# SNES_RGBAmp_1Chip03.net
KiCad netlist of a schematic drawn in EAGLE
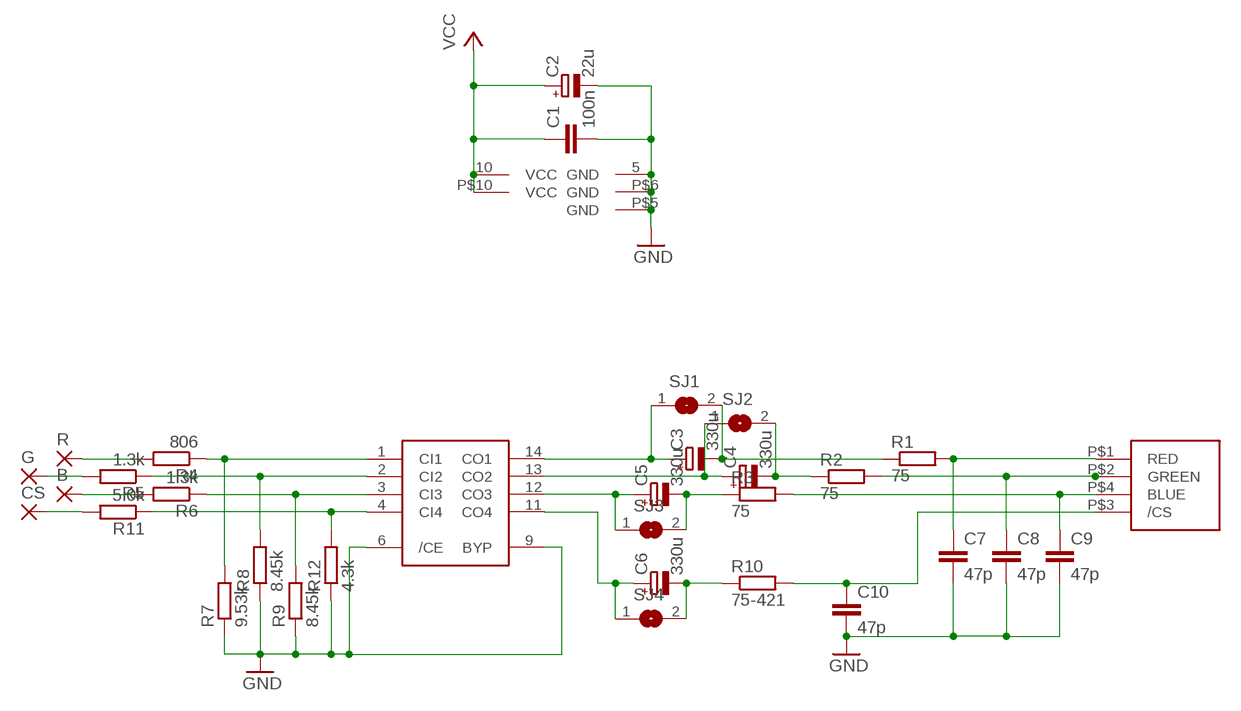
[diagram p0: schematic, sheet 1]

(export (version "E")
  (design (tool "Eeschema 10.0.6"))
  (components
    (comp (ref "B")
      (value "SMD2")
      (footprint "eagle-import:SMD1,27-2,54")
      (libsource (lib "eagle-import") (part "SMD2"))
    )
    (comp (ref "C1")
      (value "100n")
      (footprint "eagle-import:Z0805")
      (libsource (lib "eagle-import") (part "C0805"))
    )
    (comp (ref "C2")
      (value "22u")
      (footprint "eagle-import:SMC_C")
      (libsource (lib "eagle-import") (part "CPOL-EUSMCC"))
    )
    (comp (ref "C3")
      (value "330u")
      (footprint "eagle-import:SMC_D")
      (libsource (lib "eagle-import") (part "CPOL-EUSMCD"))
    )
    (comp (ref "C4")
      (value "330u")
      (footprint "eagle-import:SMC_D")
      (libsource (lib "eagle-import") (part "CPOL-EUSMCD"))
    )
    (comp (ref "C5")
      (value "330u")
      (footprint "eagle-import:SMC_D")
      (libsource (lib "eagle-import") (part "CPOL-EUSMCD"))
    )
    (comp (ref "C6")
      (value "330u")
      (footprint "eagle-import:SMC_D")
      (libsource (lib "eagle-import") (part "CPOL-EUSMCD"))
    )
    (comp (ref "C7")
      (value "47p")
      (footprint "eagle-import:Z0805")
      (libsource (lib "eagle-import") (part "C0805"))
    )
    (comp (ref "C8")
      (value "47p")
      (footprint "eagle-import:Z0805")
      (libsource (lib "eagle-import") (part "C0805"))
    )
    (comp (ref "C9")
      (value "47p")
      (footprint "eagle-import:Z0805")
      (libsource (lib "eagle-import") (part "C0805"))
    )
    (comp (ref "C10")
      (value "47p")
      (footprint "eagle-import:Z0805")
      (libsource (lib "eagle-import") (part "C0805"))
    )
    (comp (ref "CS")
      (value "SMD2")
      (footprint "eagle-import:SMD1,27-2,54")
      (libsource (lib "eagle-import") (part "SMD2"))
    )
    (comp (ref "G")
      (value "SMD2")
      (footprint "eagle-import:SMD1,27-2,54")
      (libsource (lib "eagle-import") (part "SMD2"))
    )
    (comp (ref "R")
      (value "SMD2")
      (footprint "eagle-import:SMD1,27-2,54")
      (libsource (lib "eagle-import") (part "SMD2"))
    )
    (comp (ref "R1")
      (value "75")
      (footprint "eagle-import:Z0805")
      (libsource (lib "eagle-import") (part "R0805"))
    )
    (comp (ref "R2")
      (value "75")
      (footprint "eagle-import:Z0805")
      (libsource (lib "eagle-import") (part "R0805"))
    )
    (comp (ref "R3")
      (value "75")
      (footprint "eagle-import:Z0805")
      (libsource (lib "eagle-import") (part "R0805"))
    )
    (comp (ref "R4")
      (value "806")
      (footprint "eagle-import:Z0805")
      (libsource (lib "eagle-import") (part "R0805"))
    )
    (comp (ref "R5")
      (value "1.3k")
      (footprint "eagle-import:Z0805")
      (libsource (lib "eagle-import") (part "R0805"))
    )
    (comp (ref "R6")
      (value "1.3k")
      (footprint "eagle-import:Z0805")
      (libsource (lib "eagle-import") (part "R0805"))
    )
    (comp (ref "R7")
      (value "9.53k")
      (footprint "eagle-import:Z0805")
      (libsource (lib "eagle-import") (part "R0805"))
    )
    (comp (ref "R8")
      (value "8.45k")
      (footprint "eagle-import:Z0805")
      (libsource (lib "eagle-import") (part "R0805"))
    )
    (comp (ref "R9")
      (value "8.45k")
      (footprint "eagle-import:Z0805")
      (libsource (lib "eagle-import") (part "R0805"))
    )
    (comp (ref "R10")
      (value "75-421")
      (footprint "eagle-import:Z0805")
      (libsource (lib "eagle-import") (part "R0805"))
    )
    (comp (ref "R11")
      (value "5.0k")
      (footprint "eagle-import:Z0805")
      (libsource (lib "eagle-import") (part "R0805"))
    )
    (comp (ref "R12")
      (value "4.3k")
      (footprint "eagle-import:Z0805")
      (libsource (lib "eagle-import") (part "R0805"))
    )
    (comp (ref "SJ1") (value "SJ") (footprint "eagle-import:SJ") (libsource (lib "eagle-import") (part "SJ")))
    (comp (ref "SJ2") (value "SJ") (footprint "eagle-import:SJ") (libsource (lib "eagle-import") (part "SJ")))
    (comp (ref "SJ3") (value "SJ") (footprint "eagle-import:SJ") (libsource (lib "eagle-import") (part "SJ")))
    (comp (ref "SJ4") (value "SJ") (footprint "eagle-import:SJ") (libsource (lib "eagle-import") (part "SJ")))
    (comp (ref "U$2")
      (value "THS7374")
      (footprint "eagle-import:THS7374")
      (libsource (lib "eagle-import") (part "THS7374"))
    )
    (comp (ref "U$3")
      (value "SNES_MULTIAV_RGBC_ONLY")
      (footprint "eagle-import:SNES_MULTIAV_RGBC_ONLY")
      (libsource (lib "eagle-import") (part "SNES_MULTIAV_RGBC_ONLY"))
    )
  )
  (nets
    (net (code "1") (name "GND") (class "Default")
      (node (ref "C1") (pin "2") (pinfunction "2_2") (pintype "passive"))
      (node (ref "C10") (pin "2") (pinfunction "2_2") (pintype "passive"))
      (node (ref "C2") (pin "-") (pinfunction "-_-") (pintype "passive"))
      (node (ref "C7") (pin "2") (pinfunction "2_2") (pintype "passive"))
      (node (ref "C8") (pin "2") (pinfunction "2_2") (pintype "passive"))
      (node (ref "C9") (pin "2") (pinfunction "2_2") (pintype "passive"))
      (node (ref "R12") (pin "1") (pinfunction "1_1") (pintype "passive"))
      (node (ref "R7") (pin "1") (pinfunction "1_1") (pintype "passive"))
      (node (ref "R8") (pin "1") (pinfunction "1_1") (pintype "passive"))
      (node (ref "R9") (pin "1") (pinfunction "1_1") (pintype "passive"))
      (node (ref "U$2") (pin "5") (pinfunction "GND_5") (pintype "bidirectional"))
      (node (ref "U$2") (pin "6") (pinfunction "/CE_6") (pintype "bidirectional"))
      (node (ref "U$2") (pin "9") (pinfunction "BYP_9") (pintype "bidirectional"))
      (node (ref "U$3") (pin "P$5") (pinfunction "GND_P$5") (pintype "bidirectional"))
      (node (ref "U$3") (pin "P$6") (pinfunction "GND_P$6") (pintype "bidirectional"))
    )
    (net (code "2") (name "Net-(B-P)") (class "Default")
      (node (ref "B") (pin "1") (pinfunction "P_1") (pintype "passive"))
      (node (ref "R6") (pin "2") (pinfunction "2_2") (pintype "passive"))
    )
    (net (code "3") (name "Net-(C3-Pad-)") (class "Default")
      (node (ref "C3") (pin "-") (pinfunction "-_-") (pintype "passive"))
      (node (ref "R1") (pin "1") (pinfunction "1_1") (pintype "passive"))
      (node (ref "SJ1") (pin "2") (pinfunction "2_2") (pintype "passive"))
    )
    (net (code "4") (name "Net-(C4-Pad-)") (class "Default")
      (node (ref "C4") (pin "-") (pinfunction "-_-") (pintype "passive"))
      (node (ref "R2") (pin "1") (pinfunction "1_1") (pintype "passive"))
      (node (ref "SJ2") (pin "2") (pinfunction "2_2") (pintype "passive"))
    )
    (net (code "5") (name "Net-(C5-Pad-)") (class "Default")
      (node (ref "C5") (pin "-") (pinfunction "-_-") (pintype "passive"))
      (node (ref "R3") (pin "1") (pinfunction "1_1") (pintype "passive"))
      (node (ref "SJ3") (pin "2") (pinfunction "2_2") (pintype "passive"))
    )
    (net (code "6") (name "Net-(C6-Pad-)") (class "Default")
      (node (ref "C6") (pin "-") (pinfunction "-_-") (pintype "passive"))
      (node (ref "R10") (pin "1") (pinfunction "1_1") (pintype "passive"))
      (node (ref "SJ4") (pin "2") (pinfunction "2_2") (pintype "passive"))
    )
    (net (code "7") (name "Net-(CS-P)") (class "Default")
      (node (ref "CS") (pin "1") (pinfunction "P_1") (pintype "passive"))
      (node (ref "R11") (pin "2") (pinfunction "2_2") (pintype "passive"))
    )
    (net (code "8") (name "Net-(G-P)") (class "Default")
      (node (ref "G") (pin "1") (pinfunction "P_1") (pintype "passive"))
      (node (ref "R5") (pin "2") (pinfunction "2_2") (pintype "passive"))
    )
    (net (code "9") (name "Net-(R-P)") (class "Default")
      (node (ref "R") (pin "1") (pinfunction "P_1") (pintype "passive"))
      (node (ref "R4") (pin "2") (pinfunction "2_2") (pintype "passive"))
    )
    (net (code "10") (name "Net-(U$2A-CI1)") (class "Default")
      (node (ref "R4") (pin "1") (pinfunction "1_1") (pintype "passive"))
      (node (ref "R7") (pin "2") (pinfunction "2_2") (pintype "passive"))
      (node (ref "U$2") (pin "1") (pinfunction "CI1_1") (pintype "bidirectional"))
    )
    (net (code "11") (name "Net-(U$2A-CI2)") (class "Default")
      (node (ref "R5") (pin "1") (pinfunction "1_1") (pintype "passive"))
      (node (ref "R8") (pin "2") (pinfunction "2_2") (pintype "passive"))
      (node (ref "U$2") (pin "2") (pinfunction "CI2_2") (pintype "bidirectional"))
    )
    (net (code "12") (name "Net-(U$2A-CI3)") (class "Default")
      (node (ref "R6") (pin "1") (pinfunction "1_1") (pintype "passive"))
      (node (ref "R9") (pin "2") (pinfunction "2_2") (pintype "passive"))
      (node (ref "U$2") (pin "3") (pinfunction "CI3_3") (pintype "bidirectional"))
    )
    (net (code "13") (name "Net-(U$2A-CI4)") (class "Default")
      (node (ref "R11") (pin "1") (pinfunction "1_1") (pintype "passive"))
      (node (ref "R12") (pin "2") (pinfunction "2_2") (pintype "passive"))
      (node (ref "U$2") (pin "4") (pinfunction "CI4_4") (pintype "bidirectional"))
    )
    (net (code "14") (name "Net-(U$2A-CO1)") (class "Default")
      (node (ref "C3") (pin "+") (pinfunction "+_+") (pintype "passive"))
      (node (ref "SJ1") (pin "1") (pinfunction "1_1") (pintype "passive"))
      (node (ref "U$2") (pin "14") (pinfunction "CO1_14") (pintype "bidirectional"))
    )
    (net (code "15") (name "Net-(U$2A-CO2)") (class "Default")
      (node (ref "C4") (pin "+") (pinfunction "+_+") (pintype "passive"))
      (node (ref "SJ2") (pin "1") (pinfunction "1_1") (pintype "passive"))
      (node (ref "U$2") (pin "13") (pinfunction "CO2_13") (pintype "bidirectional"))
    )
    (net (code "16") (name "Net-(U$2A-CO3)") (class "Default")
      (node (ref "C5") (pin "+") (pinfunction "+_+") (pintype "passive"))
      (node (ref "SJ3") (pin "1") (pinfunction "1_1") (pintype "passive"))
      (node (ref "U$2") (pin "12") (pinfunction "CO3_12") (pintype "bidirectional"))
    )
    (net (code "17") (name "Net-(U$2A-CO4)") (class "Default")
      (node (ref "C6") (pin "+") (pinfunction "+_+") (pintype "passive"))
      (node (ref "SJ4") (pin "1") (pinfunction "1_1") (pintype "passive"))
      (node (ref "U$2") (pin "11") (pinfunction "CO4_11") (pintype "bidirectional"))
    )
    (net (code "18") (name "Net-(U$3A-BLUE)") (class "Default")
      (node (ref "C9") (pin "1") (pinfunction "1_1") (pintype "passive"))
      (node (ref "R3") (pin "2") (pinfunction "2_2") (pintype "passive"))
      (node (ref "U$3") (pin "P$4") (pinfunction "BLUE_P$4") (pintype "bidirectional"))
    )
    (net (code "19") (name "Net-(U$3A-GREEN)") (class "Default")
      (node (ref "C8") (pin "1") (pinfunction "1_1") (pintype "passive"))
      (node (ref "R2") (pin "2") (pinfunction "2_2") (pintype "passive"))
      (node (ref "U$3") (pin "P$2") (pinfunction "GREEN_P$2") (pintype "bidirectional"))
    )
    (net (code "20") (name "Net-(U$3A-RED)") (class "Default")
      (node (ref "C7") (pin "1") (pinfunction "1_1") (pintype "passive"))
      (node (ref "R1") (pin "2") (pinfunction "2_2") (pintype "passive"))
      (node (ref "U$3") (pin "P$1") (pinfunction "RED_P$1") (pintype "bidirectional"))
    )
    (net (code "21") (name "Net-(U$3A-{slash}CS)") (class "Default")
      (node (ref "C10") (pin "1") (pinfunction "1_1") (pintype "passive"))
      (node (ref "R10") (pin "2") (pinfunction "2_2") (pintype "passive"))
      (node (ref "U$3") (pin "P$3") (pinfunction "/CS_P$3") (pintype "bidirectional"))
    )
    (net (code "22") (name "VCC") (class "Default")
      (node (ref "C1") (pin "1") (pinfunction "1_1") (pintype "passive"))
      (node (ref "C2") (pin "+") (pinfunction "+_+") (pintype "passive"))
      (node (ref "U$2") (pin "10") (pinfunction "VCC_10") (pintype "bidirectional"))
      (node (ref "U$3") (pin "P$10") (pinfunction "VCC_P$10") (pintype "bidirectional"))
    )
  )
)
